# Buzzer.net
KiCad netlist of a schematic drawn in Altium Designer
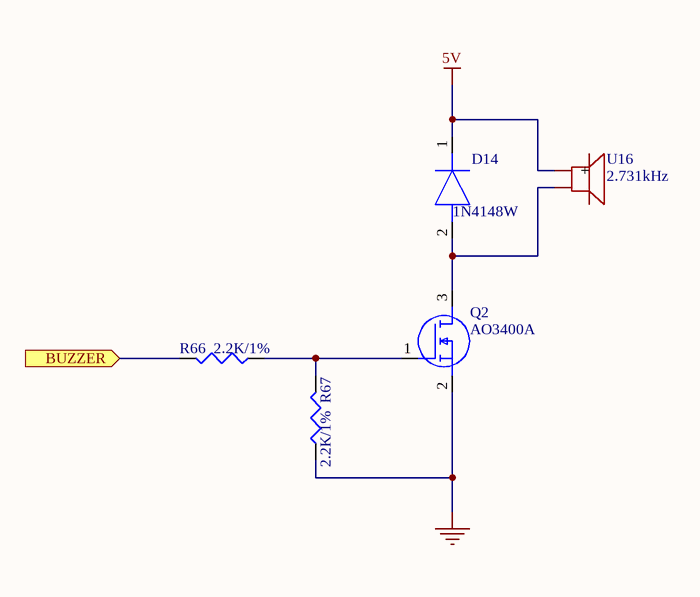
[diagram p0: Buzzer.SchDoc]

(export (version "E")
  (design (tool "Eeschema 10.0.6"))
  (components
    (comp (ref "D14")
      (value "1N4148W")
      (footprint "1N4148WVGS08")
      (description "Diode")
      (fields
        (field (name "MANUFACTURER_PART_NUMBER") "1N4148W-V-GS08")
        (field (name "MOUSER PART NUMBER") "625-1N4148W-V")
      )
      (libsource (lib "VESC_DEVICE_Library") (part "1N4148W-V-GS08"))
    )
    (comp (ref "Q2")
      (value "AO3400A")
      (footprint "SOT95P280X125-3N")
      (description "MOSFET (N-Channel)")
      (libsource (lib "VESC_DEVICE_Library") (part "AO3400A"))
    )
    (comp (ref "R66") (value "2.2K/1%") (footprint "R0402") (libsource (lib "*") (part "RESISTOR")))
    (comp (ref "R67") (value "2.2K/1%") (footprint "R0402") (libsource (lib "*") (part "RESISTOR")))
    (comp (ref "U16")
      (value "2.731kHz")
      (footprint "BUZ-SMD_4P-L7.5-W7.5-BR")
      (fields (field (name "MANUFACTURER") "HYDZ(华宇)") (field (name "MANUFACTURER PART") "HYG-7525A"))
      (libsource (lib "VESC_DEVICE_Library") (part "HYG-7525A"))
    )
  )
  (nets
    (net (code "1") (name "/BUZZER") (class "Default")
      (node (ref "R66") (pin "2") (pinfunction "2_2") (pintype "passive"))
    )
    (net (code "2") (name "5V") (class "Default")
      (node (ref "D14") (pin "1") (pinfunction "K_1") (pintype "passive"))
      (node (ref "U16") (pin "1") (pinfunction "+_1") (pintype "passive"))
    )
    (net (code "3") (name "GND") (class "Default")
      (node (ref "Q2") (pin "2") (pinfunction "S_2") (pintype "passive"))
      (node (ref "R67") (pin "1") (pinfunction "1_1") (pintype "passive"))
    )
    (net (code "4") (name "Net-(D14-A)") (class "Default")
      (node (ref "D14") (pin "2") (pinfunction "A_2") (pintype "passive"))
      (node (ref "Q2") (pin "3") (pinfunction "D_3") (pintype "passive"))
      (node (ref "U16") (pin "2") (pinfunction "2_2") (pintype "passive"))
    )
    (net (code "5") (name "Net-(Q2-G)") (class "Default")
      (node (ref "Q2") (pin "1") (pinfunction "G_1") (pintype "passive"))
      (node (ref "R66") (pin "1") (pinfunction "1_1") (pintype "passive"))
      (node (ref "R67") (pin "2") (pinfunction "2_2") (pintype "passive"))
    )
    (net (code "6") (name "unconnected-(U16-Pad3)") (class "Default")
      (node (ref "U16") (pin "3") (pinfunction "3_3") (pintype "passive"))
    )
    (net (code "7") (name "unconnected-(U16-Pad4)") (class "Default")
      (node (ref "U16") (pin "4") (pinfunction "4_4") (pintype "passive"))
    )
  )
)
